# Main.net
KiCad netlist of a schematic drawn in Altium Designer
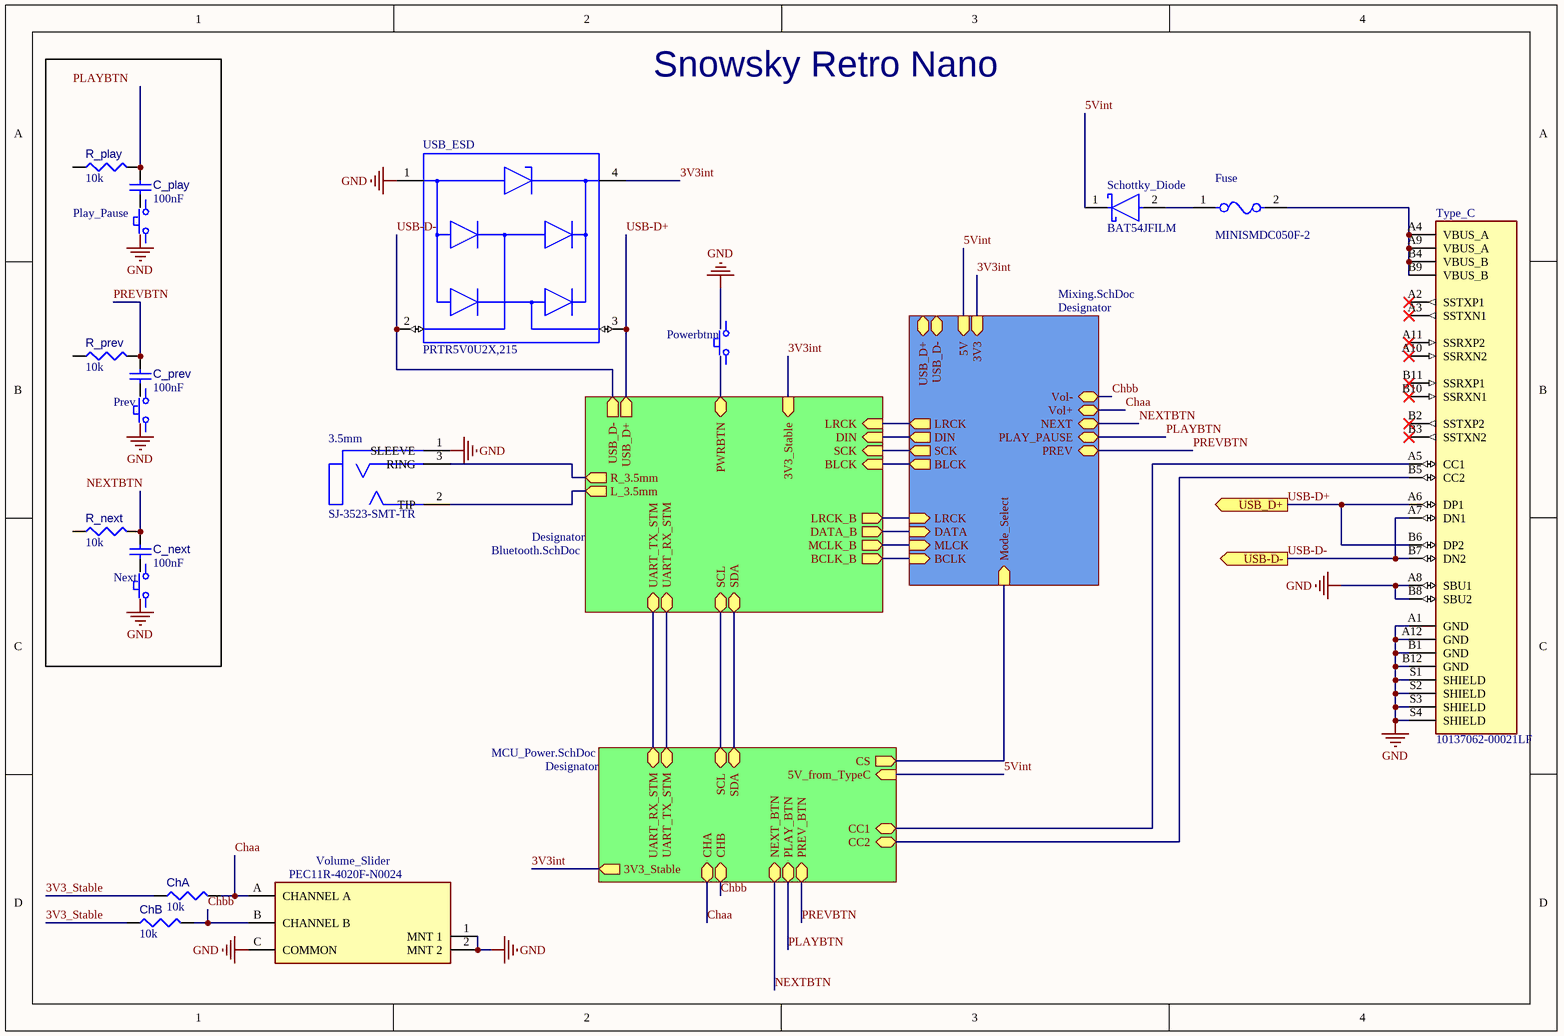
[diagram p0: Main.SchDoc]

(export (version "E")
  (design (tool "Eeschema 10.0.6"))
  (components
    (comp (ref "3.5mm")
      (value "SJ-3523-SMT-TR")
      (footprint "CUI_SJ-3523-SMT-TR")
      (fields (field (name "MF") "Same Sky"))
      (libsource (lib "Sripathy Siddartha") (part "SJ-3523-SMT-TR"))
    )
    (comp (ref "ChA")
      (value "10k")
      (footprint "RESC0402(1005)_L")
      (description "10K 0.063W 1% 0402 (1005 Metric)  SMD")
      (fields (field (name "POWER") "63mW") (field (name "TOLERANCE") "1%"))
      (libsource (lib "Sripathy Siddartha") (part "10KR2F"))
    )
    (comp (ref "ChB")
      (value "10k")
      (footprint "RESC0402(1005)_L")
      (description "10K 0.063W 1% 0402 (1005 Metric)  SMD")
      (fields (field (name "POWER") "63mW") (field (name "TOLERANCE") "1%"))
      (libsource (lib "Sripathy Siddartha") (part "10KR2F"))
    )
    (comp (ref "C_next")
      (value "100nF")
      (footprint "CAPC0402(1005)60_L")
      (description "Chip Capacitor, 100nF +/-20%, 10V, 0402, Thickness 0.6 mm")
      (fields (field (name "TOLERANCE") "20%") (field (name "Comment") "Capacitor 100nF +/-20% 10V 0402"))
      (libsource (lib "Sripathy Siddartha") (part "CAP-NP-2"))
    )
    (comp (ref "C_play")
      (value "100nF")
      (footprint "CAPC0402(1005)60_L")
      (description "Chip Capacitor, 100nF +/-20%, 10V, 0402, Thickness 0.6 mm")
      (fields (field (name "TOLERANCE") "20%") (field (name "Comment") "Capacitor 100nF +/-20% 10V 0402"))
      (libsource (lib "Sripathy Siddartha") (part "CAP-NP-2"))
    )
    (comp (ref "C_prev")
      (value "100nF")
      (footprint "CAPC0402(1005)60_L")
      (description "Chip Capacitor, 100nF +/-20%, 10V, 0402, Thickness 0.6 mm")
      (fields (field (name "TOLERANCE") "20%") (field (name "Comment") "Capacitor 100nF +/-20% 10V 0402"))
      (libsource (lib "Sripathy Siddartha") (part "CAP-NP-2"))
    )
    (comp (ref "Fuse")
      (value "MINISMDC050F-2")
      (footprint "FP-MINISMDC050F-MFG")
      (description "PTC RESET FUSE 24V 500MA 1812")
      (fields
        (field (name "MANUFACTURER") "Littelfuse")
        (field (name "OCTOPART") "https://octopart.com/minismdc050f-2-littelfuse-74215011")
      )
      (libsource (lib "Altium Content Vault") (part "5bcf9b9f640e542cf0359d10258e979"))
    )
    (comp (ref "Next")
      (value "MSP103C04")
      (footprint "FP-MSP103C04-MFG")
      (description "SWITCH PUSH SPST-NO 3A 125V")
      (libsource (lib "Altium Content Vault") (part "3a7ffd2e40b3115a6201d475c2ec4a5"))
    )
    (comp (ref "Play_Pause")
      (value "MSP103C04")
      (footprint "FP-MSP103C04-MFG")
      (description "SWITCH PUSH SPST-NO 3A 125V")
      (libsource (lib "Altium Content Vault") (part "3a7ffd2e40b3115a6201d475c2ec4a5"))
    )
    (comp (ref "Powerbtnn")
      (value "MSP103C04")
      (footprint "FP-MSP103C04-MFG")
      (description "SWITCH PUSH SPST-NO 3A 125V")
      (libsource (lib "Altium Content Vault") (part "3a7ffd2e40b3115a6201d475c2ec4a5"))
    )
    (comp (ref "Prev")
      (value "MSP103C04")
      (footprint "FP-MSP103C04-MFG")
      (description "SWITCH PUSH SPST-NO 3A 125V")
      (libsource (lib "Altium Content Vault") (part "3a7ffd2e40b3115a6201d475c2ec4a5"))
    )
    (comp (ref "R_next")
      (value "10k")
      (footprint "RESC0402(1005)_L")
      (description "10K 0.063W 1% 0402 (1005 Metric)  SMD")
      (fields (field (name "POWER") "63mW") (field (name "TOLERANCE") "1%"))
      (libsource (lib "Sripathy Siddartha") (part "10KR2F"))
    )
    (comp (ref "R_play")
      (value "10k")
      (footprint "RESC0402(1005)_L")
      (description "10K 0.063W 1% 0402 (1005 Metric)  SMD")
      (fields (field (name "POWER") "63mW") (field (name "TOLERANCE") "1%"))
      (libsource (lib "Sripathy Siddartha") (part "10KR2F"))
    )
    (comp (ref "R_prev")
      (value "10k")
      (footprint "RESC0402(1005)_L")
      (description "10K 0.063W 1% 0402 (1005 Metric)  SMD")
      (fields (field (name "POWER") "63mW") (field (name "TOLERANCE") "1%"))
      (libsource (lib "Sripathy Siddartha") (part "10KR2F"))
    )
    (comp (ref "Schottky_Diode")
      (value "BAT54JFILM")
      (footprint "FP-SOD323-MFG")
      (description "DIODE SCHOTTKY 40V 300MA SOD323")
      (fields
        (field (name "OCTOPART") "https://octopart.com/bat54jfilm-stmicroelectronics-326073")
        (field (name "MANUFACTURER") "STMicroelectronics")
      )
      (libsource (lib "Altium Content Vault") (part "1d6ec82d83fb6aee721767c19dac4b9"))
    )
    (comp (ref "Type_C")
      (value "10137062-00021LF")
      (footprint "AMPHENOL_10137062-00021LF")
      (fields (field (name "MF") "Amphenol") (field (name "MP") "1013706200021LF"))
      (libsource (lib "Sripathy Siddartha") (part "10137062-00021LF"))
    )
    (comp (ref "USB_ESD")
      (value "PRTR5V0U2X,215")
      (footprint "FP-SOT143B-MFG")
      (description "TVS DIODE 5.5V SOT143B")
      (libsource (lib "Altium Content Vault") (part "31e4fa1655694efd507c8a671e666ef"))
    )
    (comp (ref "Volume_Slider")
      (value "PEC11R-4020F-N0024")
      (footprint "FP-PEC11R-4020F-N0024-MFG")
      (description "ROTARY ENCODER MECHANICAL 24PPR")
      (libsource (lib "Altium Content Vault") (part "b4abdab4eeac4949451e561538c91ea"))
    )
  )
  (nets
    (net (code "1") (name "/3V3_Stable") (class "Default")
      (node (ref "ChA") (pin "1") (pinfunction "1_1") (pintype "passive"))
      (node (ref "ChB") (pin "1") (pinfunction "1_1") (pintype "passive"))
    )
    (net (code "2") (name "/3V3int") (class "Default")
      (node (ref "USB_ESD") (pin "4") (pinfunction "VCC_4") (pintype "power_in"))
    )
    (net (code "3") (name "/5Vint") (class "Default")
      (node (ref "Schottky_Diode") (pin "1") (pinfunction "C_1") (pintype "passive"))
    )
    (net (code "6") (name "/CC1") (class "Default")
      (node (ref "Type_C") (pin "A5") (pinfunction "CC1_A5") (pintype "bidirectional"))
    )
    (net (code "7") (name "/CC2") (class "Default")
      (node (ref "Type_C") (pin "B5") (pinfunction "CC2_B5") (pintype "bidirectional"))
    )
    (net (code "9") (name "/Chaa") (class "Default")
      (node (ref "ChA") (pin "2") (pinfunction "2_2") (pintype "passive"))
      (node (ref "Volume_Slider") (pin "A") (pinfunction "CHANNEL_A_A") (pintype "passive"))
    )
    (net (code "10") (name "/Chbb") (class "Default")
      (node (ref "ChB") (pin "2") (pinfunction "2_2") (pintype "passive"))
      (node (ref "Volume_Slider") (pin "B") (pinfunction "CHANNEL_B_B") (pintype "passive"))
    )
    (net (code "15") (name "/L_3.5mm") (class "Default")
      (node (ref "3.5mm") (pin "2") (pinfunction "TIP_2") (pintype "passive"))
    )
    (net (code "19") (name "/PREVBTN") (class "Default")
      (node (ref "C_prev") (pin "2") (pinfunction "2_2") (pintype "passive"))
      (node (ref "R_prev") (pin "2") (pinfunction "2_2") (pintype "passive"))
    )
    (net (code "21") (name "/R_3.5mm") (class "Default")
      (node (ref "3.5mm") (pin "3") (pinfunction "RING_3") (pintype "passive"))
    )
    (net (code "27") (name "/USB-D+") (class "Default")
      (node (ref "Type_C") (pin "A6") (pinfunction "DP1_A6") (pintype "bidirectional"))
      (node (ref "Type_C") (pin "B6") (pinfunction "DP2_B6") (pintype "bidirectional"))
      (node (ref "USB_ESD") (pin "3") (pinfunction "I/O_2_3") (pintype "bidirectional"))
    )
    (net (code "28") (name "/USB-D-") (class "Default")
      (node (ref "Type_C") (pin "A7") (pinfunction "DN1_A7") (pintype "bidirectional"))
      (node (ref "Type_C") (pin "B7") (pinfunction "DN2_B7") (pintype "bidirectional"))
      (node (ref "USB_ESD") (pin "2") (pinfunction "I/O_1_2") (pintype "bidirectional"))
    )
    (net (code "30") (name "GND") (class "Default")
      (node (ref "3.5mm") (pin "1") (pinfunction "SLEEVE_1") (pintype "passive"))
      (node (ref "Type_C") (pin "A1") (pinfunction "GND_A1") (pintype "power_in"))
      (node (ref "Type_C") (pin "A12") (pinfunction "GND_A12") (pintype "power_in"))
      (node (ref "Type_C") (pin "A8") (pinfunction "SBU1_A8") (pintype "bidirectional"))
      (node (ref "Type_C") (pin "B1") (pinfunction "GND_B1") (pintype "power_in"))
      (node (ref "Type_C") (pin "B12") (pinfunction "GND_B12") (pintype "power_in"))
      (node (ref "Type_C") (pin "B8") (pinfunction "SBU2_B8") (pintype "bidirectional"))
      (node (ref "Type_C") (pin "S1") (pinfunction "SHIELD_S1") (pintype "power_in"))
      (node (ref "Type_C") (pin "S2") (pinfunction "SHIELD_S2") (pintype "power_in"))
      (node (ref "Type_C") (pin "S3") (pinfunction "SHIELD_S3") (pintype "power_in"))
      (node (ref "Type_C") (pin "S4") (pinfunction "SHIELD_S4") (pintype "power_in"))
      (node (ref "USB_ESD") (pin "1") (pinfunction "GND_1") (pintype "power_in"))
      (node (ref "Volume_Slider") (pin "1") (pinfunction "MNT_1_1") (pintype "passive"))
      (node (ref "Volume_Slider") (pin "2") (pinfunction "MNT_2_2") (pintype "passive"))
      (node (ref "Volume_Slider") (pin "C") (pinfunction "COMMON_C") (pintype "passive"))
    )
    (net (code "31") (name "Net-(C_next-Pad2)") (class "Default")
      (node (ref "C_next") (pin "2") (pinfunction "2_2") (pintype "passive"))
      (node (ref "R_next") (pin "2") (pinfunction "2_2") (pintype "passive"))
    )
    (net (code "32") (name "Net-(C_play-Pad2)") (class "Default")
      (node (ref "C_play") (pin "2") (pinfunction "2_2") (pintype "passive"))
      (node (ref "R_play") (pin "2") (pinfunction "2_2") (pintype "passive"))
    )
    (net (code "33") (name "Net-(Fuse-Pad2)") (class "Default")
      (node (ref "Fuse") (pin "2") (pinfunction "2_2") (pintype "passive"))
      (node (ref "Type_C") (pin "A4") (pinfunction "VBUS_A_A4") (pintype "power_in"))
      (node (ref "Type_C") (pin "A9") (pinfunction "VBUS_A_A9") (pintype "power_in"))
      (node (ref "Type_C") (pin "B4") (pinfunction "VBUS_B_B4") (pintype "power_in"))
      (node (ref "Type_C") (pin "B9") (pinfunction "VBUS_B_B9") (pintype "power_in"))
    )
    (net (code "34") (name "Net-(Schottky_Diode-A)") (class "Default")
      (node (ref "Fuse") (pin "1") (pinfunction "1_1") (pintype "passive"))
      (node (ref "Schottky_Diode") (pin "2") (pinfunction "A_2") (pintype "passive"))
    )
    (net (code "35") (name "unconnected-(C_next-Pad1)") (class "Default")
      (node (ref "C_next") (pin "1") (pinfunction "1_1") (pintype "passive"))
    )
    (net (code "36") (name "unconnected-(C_play-Pad1)") (class "Default")
      (node (ref "C_play") (pin "1") (pinfunction "1_1") (pintype "passive"))
    )
    (net (code "37") (name "unconnected-(C_prev-Pad1)") (class "Default")
      (node (ref "C_prev") (pin "1") (pinfunction "1_1") (pintype "passive"))
    )
    (net (code "38") (name "unconnected-(R_next-Pad1)") (class "Default")
      (node (ref "R_next") (pin "1") (pinfunction "1_1") (pintype "passive"))
    )
    (net (code "39") (name "unconnected-(R_play-Pad1)") (class "Default")
      (node (ref "R_play") (pin "1") (pinfunction "1_1") (pintype "passive"))
    )
    (net (code "40") (name "unconnected-(R_prev-Pad1)") (class "Default")
      (node (ref "R_prev") (pin "1") (pinfunction "1_1") (pintype "passive"))
    )
    (net (code "41") (name "unconnected-(Type_C-SSRXN1-PadB10)") (class "Default")
      (node (ref "Type_C") (pin "B10") (pinfunction "SSRXN1_B10") (pintype "input+no_connect"))
    )
    (net (code "42") (name "unconnected-(Type_C-SSRXN2-PadA10)") (class "Default")
      (node (ref "Type_C") (pin "A10") (pinfunction "SSRXN2_A10") (pintype "input+no_connect"))
    )
    (net (code "43") (name "unconnected-(Type_C-SSRXP1-PadB11)") (class "Default")
      (node (ref "Type_C") (pin "B11") (pinfunction "SSRXP1_B11") (pintype "input+no_connect"))
    )
    (net (code "44") (name "unconnected-(Type_C-SSRXP2-PadA11)") (class "Default")
      (node (ref "Type_C") (pin "A11") (pinfunction "SSRXP2_A11") (pintype "input+no_connect"))
    )
    (net (code "45") (name "unconnected-(Type_C-SSTXN1-PadA3)") (class "Default")
      (node (ref "Type_C") (pin "A3") (pinfunction "SSTXN1_A3") (pintype "output+no_connect"))
    )
    (net (code "46") (name "unconnected-(Type_C-SSTXN2-PadB3)") (class "Default")
      (node (ref "Type_C") (pin "B3") (pinfunction "SSTXN2_B3") (pintype "output+no_connect"))
    )
    (net (code "47") (name "unconnected-(Type_C-SSTXP1-PadA2)") (class "Default")
      (node (ref "Type_C") (pin "A2") (pinfunction "SSTXP1_A2") (pintype "output+no_connect"))
    )
    (net (code "48") (name "unconnected-(Type_C-SSTXP2-PadB2)") (class "Default")
      (node (ref "Type_C") (pin "B2") (pinfunction "SSTXP2_B2") (pintype "output+no_connect"))
    )
  )
)
